# Cell.net
KiCad netlist of a schematic drawn in Altium Designer
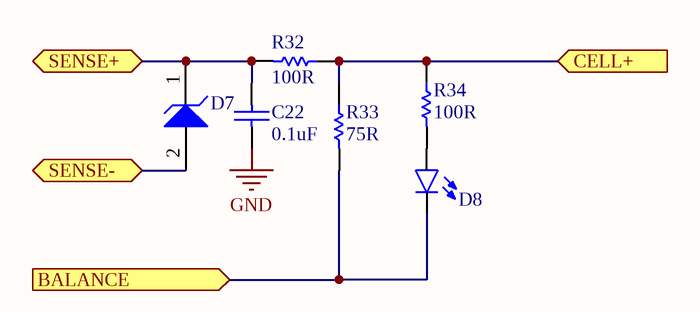
[diagram p0: Cell.SchDoc]

(export (version "E")
  (design (tool "Eeschema 10.0.6"))
  (components
    (comp (ref "C22")
      (value "0.1uF")
      (footprint "C0402[1005X55]")
      (description "0.1uF 6.3V 10% 0402 (1005 Metric)")
      (fields (field (name "TOLERANCE") "10%") (field (name "PARTNUMBER") "GRM155R70J104KA01D"))
      (libsource (lib "Capacitors") (part "CAP_0.1uF_6.3V_0402_10%"))
    )
    (comp (ref "D7")
      (value "MM3Z12VT1G")
      (footprint "ONSC-SOD-323-2-477-02_V")
      (description "Zener Voltage Regulator, 300 mW, 2-Pin SOD-323, Tape and Reel")
      (fields (field (name "MANUFACTURER") "On Semiconductor"))
      (libsource (lib "Altium Content Vault") (part "CMP-1060-00726-1"))
    )
    (comp (ref "D8")
      (value "LED_0603")
      (footprint "LED0603")
      (fields (field (name "PARTNUMBER") "LTST-C193TBKT-5A") (field (name "MANUFACTURER") "Lite-On Inc."))
      (libsource (lib "LEDs-0603") (part "LED_0603"))
    )
    (comp (ref "R32")
      (value "100R")
      (footprint "R0402[1005]")
      (description "100R 0.063W 1% 0402 (1005 Metric)")
      (fields (field (name "POWER") "0.063W") (field (name "TOLERANCE") "1%"))
      (libsource (lib "Resistors") (part "RES_100R_0402_1%"))
    )
    (comp (ref "R33")
      (value "75R")
      (footprint "R0603[1608]")
      (description "75R 0.25W 1% 0603 (1005 Metric)")
      (fields (field (name "TOLERANCE") "1%") (field (name "POWER") "0.25W"))
      (libsource (lib "Resistors") (part "RES_75R_0603_1%"))
    )
    (comp (ref "R34")
      (value "100R")
      (footprint "R0402[1005]")
      (description "100R 0.063W 1% 0402 (1005 Metric)")
      (fields (field (name "MANUFACTURER") "KOA Speer") (field (name "PARTNUMBER") "RK73H1ETTP1000F"))
      (libsource (lib "Resistors") (part "RES_100R_0402_1%"))
    )
  )
  (nets
    (net (code "1") (name "/BALANCE") (class "Default")
      (node (ref "D8") (pin "C") (pinfunction "C_C") (pintype "passive"))
      (node (ref "R33") (pin "1") (pinfunction "1_1") (pintype "passive"))
    )
    (net (code "2") (name "/CELL+") (class "Default")
      (node (ref "R32") (pin "2") (pinfunction "2_2") (pintype "passive"))
      (node (ref "R33") (pin "2") (pinfunction "2_2") (pintype "passive"))
      (node (ref "R34") (pin "2") (pinfunction "2_2") (pintype "passive"))
    )
    (net (code "3") (name "/SENSE+") (class "Default")
      (node (ref "C22") (pin "2") (pinfunction "2_2") (pintype "passive"))
      (node (ref "D7") (pin "1") (pinfunction "K_1") (pintype "passive"))
      (node (ref "R32") (pin "1") (pinfunction "1_1") (pintype "passive"))
    )
    (net (code "4") (name "/SENSE-") (class "Default")
      (node (ref "D7") (pin "2") (pinfunction "A_2") (pintype "passive"))
    )
    (net (code "5") (name "GND") (class "Default")
      (node (ref "C22") (pin "1") (pinfunction "1_1") (pintype "passive"))
    )
    (net (code "6") (name "Net-(D8-PadA)") (class "Default")
      (node (ref "D8") (pin "A") (pinfunction "A_A") (pintype "passive"))
      (node (ref "R34") (pin "1") (pinfunction "1_1") (pintype "passive"))
    )
  )
)
